# ProProject_module_robot-.net
KiCad netlist of a schematic drawn in EasyEDA Pro
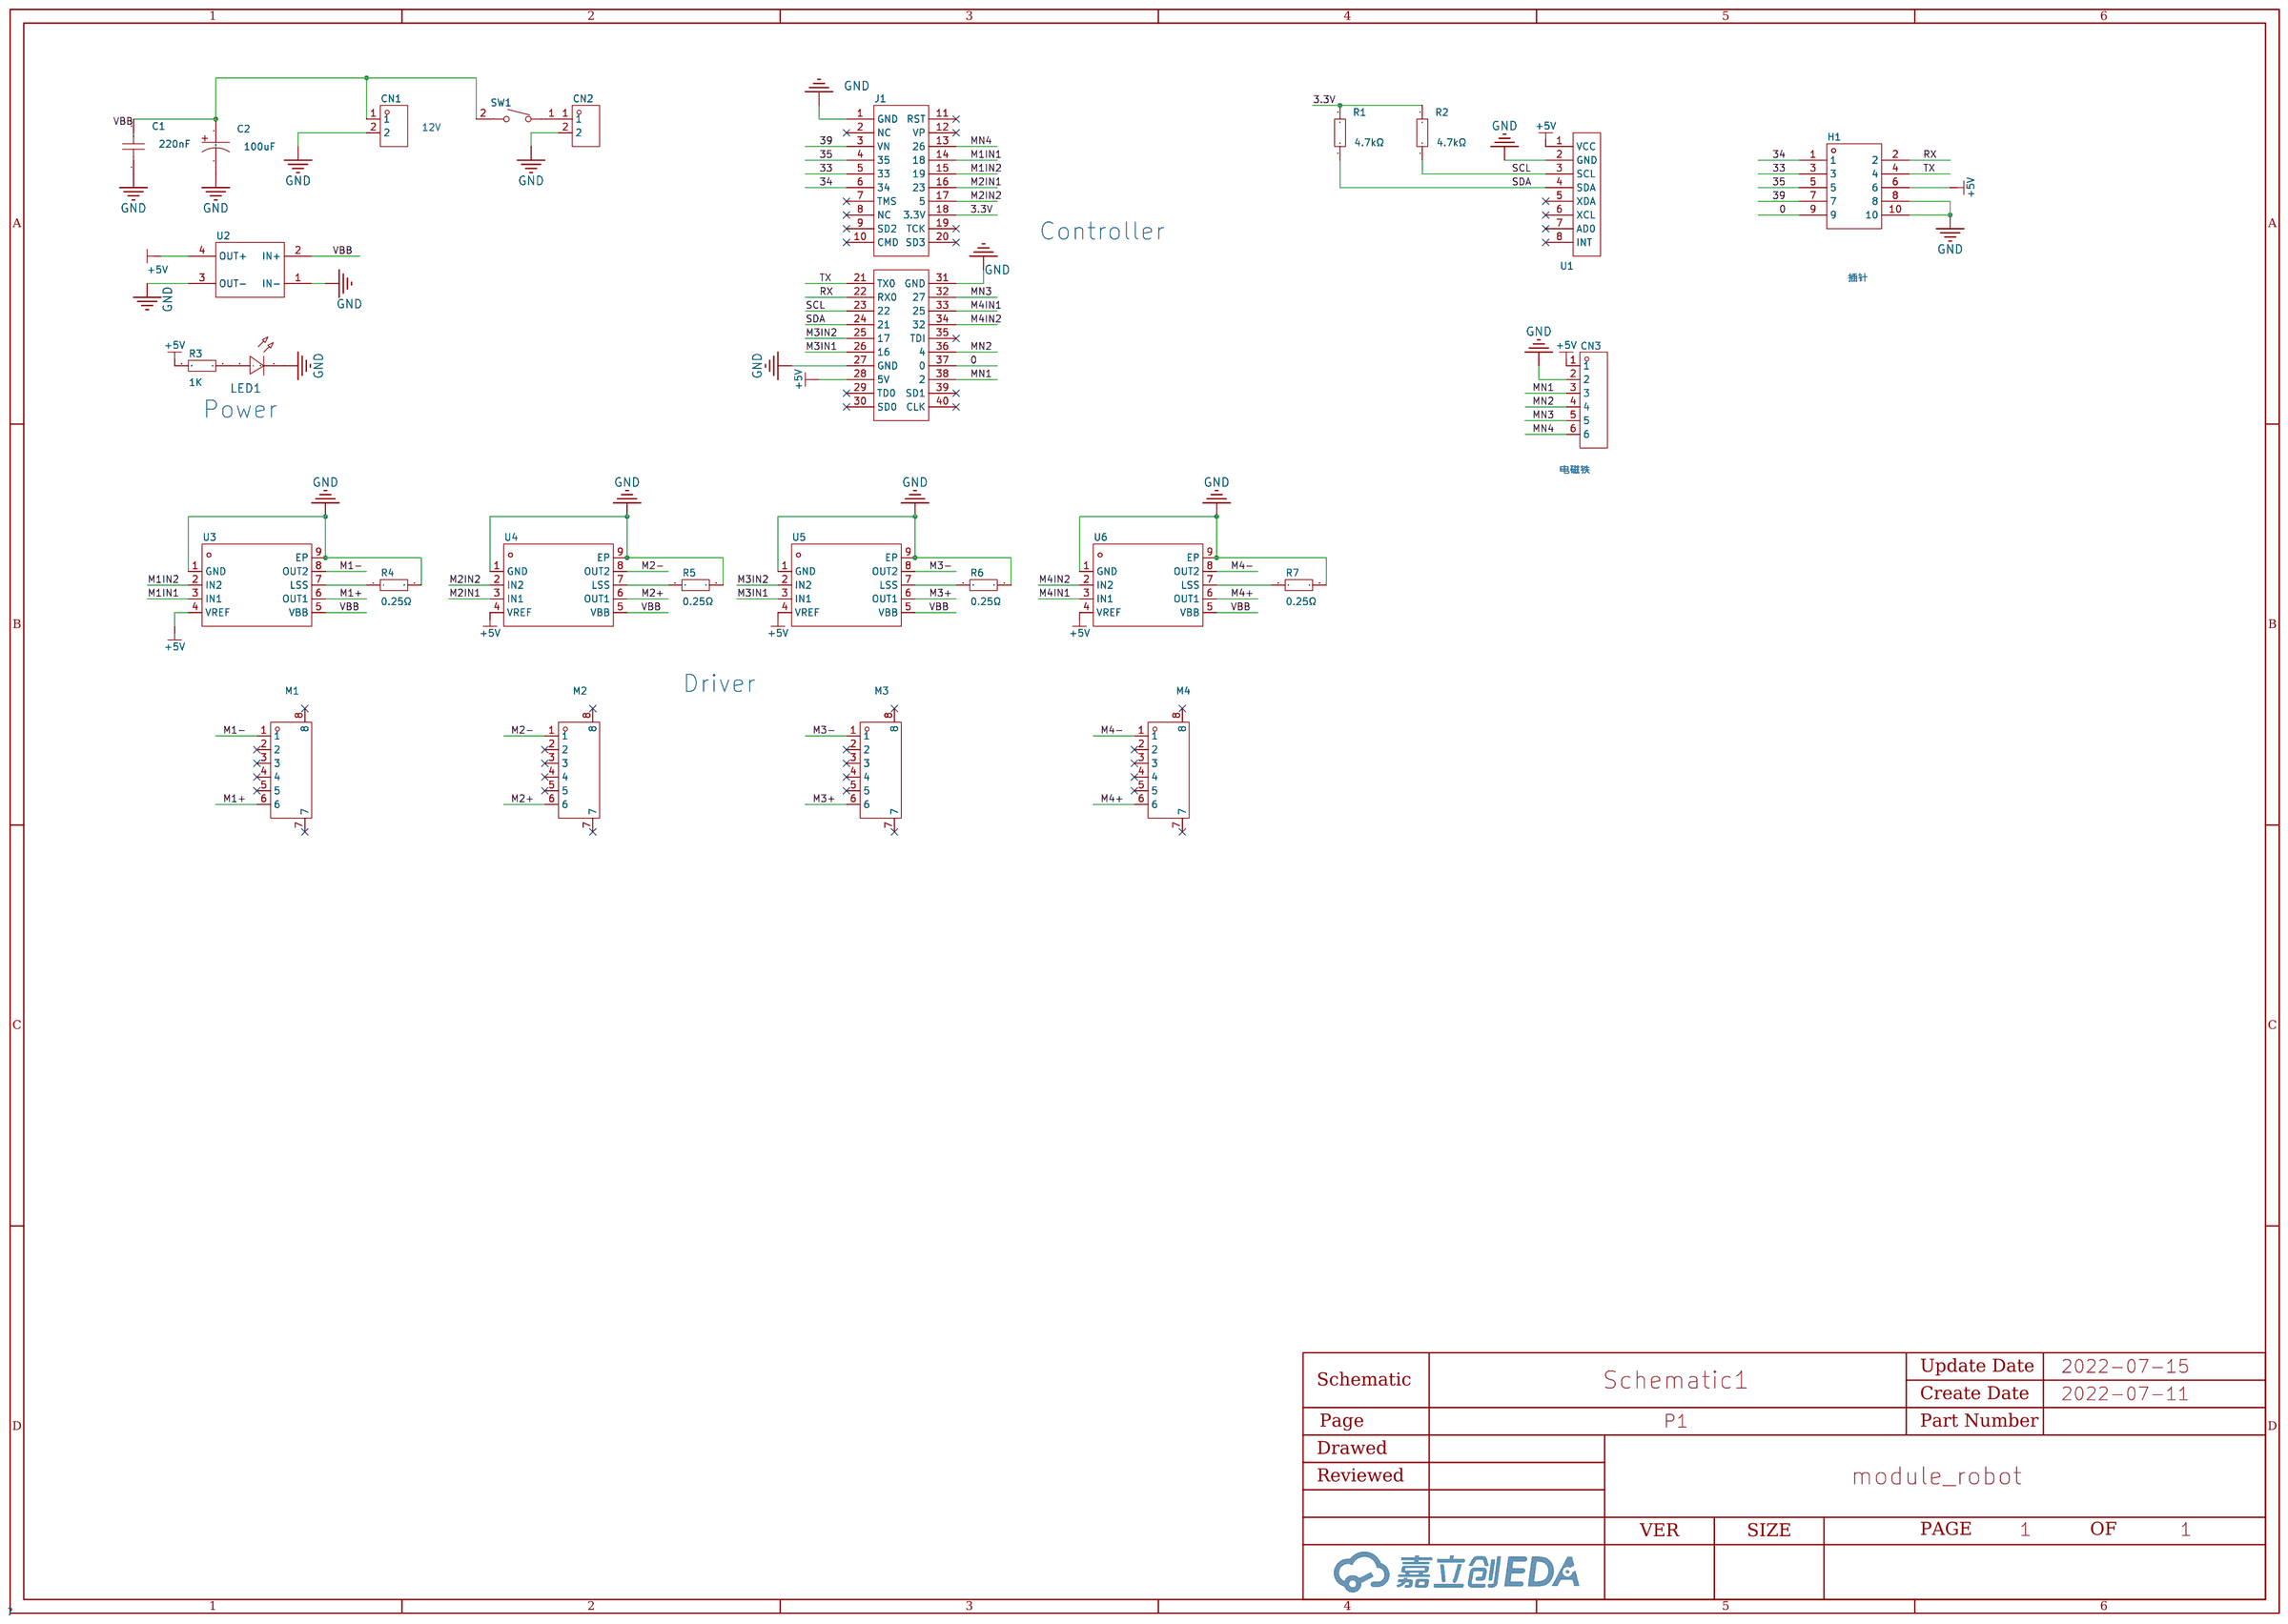
[diagram p0: schematic sheet]

(export (version "E")
  (design (tool "Eeschema 10.0.6"))
  (components
    (comp (ref "C1")
      (value "220nF")
      (description "容值:220nF;精度:±20%;额定电压:25V;温度系数:X5R;")
      (fields
        (field (name "Manufacturer Part") "TCC0603X5R224M250CT")
        (field (name "Manufacturer") "CCTC(三环)")
      )
      (libsource (lib "easyedapro") (part "TCC0603X5R224M250CT"))
    )
    (comp (ref "C2")
      (value "100uF")
      (footprint "easyedapro:CAP-TH_BD8.0-P3.50-D0.6-FD")
      (description "电容体长度:12mm;工作寿命:7000hrs 105;额定电压:50V;精度:±20%;容值:100uF;脚间距:3.5mm;电容体直径:8mm;工作温度:-;")
      (fields
        (field (name "Manufacturer Part") "RG050M101LO8*12TA-1A1E")
        (field (name "Manufacturer") "BERYL(绿宝石)")
      )
      (libsource (lib "easyedapro") (part "RG050M101LO8*12TA-1A1E"))
    )
    (comp (ref "CN1")
      (value "~")
      (footprint "easyedapro:CONN-TH_2P-P2.50_HCTL_HC-5264-2A")
      (description "参考系列:-;间距:2.5mm;插针结构:1x2P;排数:1;每排PIN数:2;行距:-;公母:公型插针;安装方式:直插;额定电流:3A;工作温度范围:-25~+85;")
      (fields (field (name "Manufacturer Part") "HC-5264-2A") (field (name "Manufacturer") "HCTL(华灿天禄)"))
      (libsource (lib "easyedapro") (part "HC-5264-2A"))
    )
    (comp (ref "CN2")
      (value "~")
      (footprint "easyedapro:CONN-TH_2P-P2.50_HCTL_HC-5264-2A")
      (description "参考系列:-;间距:2.5mm;插针结构:1x2P;排数:1;每排PIN数:2;行距:-;公母:公型插针;安装方式:直插;额定电流:3A;工作温度范围:-25~+85;")
      (fields (field (name "Manufacturer Part") "HC-5264-2A") (field (name "Manufacturer") "HCTL(华灿天禄)"))
      (libsource (lib "easyedapro") (part "HC-5264-2A"))
    )
    (comp (ref "CN3")
      (value "~")
      (footprint "easyedapro:CONN-TH_6P-P2.50_HCTL_HC-5264-6A")
      (description "参考系列:-;间距:2.5mm;插针结构:1x6P;排数:1;每排PIN数:6;行距:-;公母:公型插针;安装方式:直插;额定电流:3A;工作温度范围:-25~+85;")
      (fields (field (name "Manufacturer Part") "HC-5264-6A") (field (name "Manufacturer") "HCTL(华灿天禄)"))
      (libsource (lib "easyedapro") (part "HC-5264-6A"))
    )
    (comp (ref "H1")
      (value "~")
      (footprint "easyedapro:HDR-TH_10P-P2.54-V-M-R2-C5-S2.54")
      (libsource (lib "easyedapro") (part "HDR-M-2.54_2x5"))
    )
    (comp (ref "J1")
      (value "~")
      (description "esp32TTGO扩展封装")
      (libsource (lib "easyedapro") (part "esp32TTGO"))
    )
    (comp (ref "LED1")
      (value "~")
      (footprint "easyedapro:LED0603-RD_BLUE")
      (libsource (lib "easyedapro") (part "LED_R"))
    )
    (comp (ref "M1")
      (value "~")
      (description "参考系列:-;间距:1.5mm;插针结构:1x6P;排数:1;每排PIN数:6;行距:-;公母:公型插针;安装方式:卧贴;额定电流:500mA;工作温度范围:-25~+85;")
      (fields
        (field (name "Manufacturer Part") "KH-ZH1.5WF-06A")
        (field (name "Manufacturer") "kinghelm(金航标)")
      )
      (libsource (lib "easyedapro") (part "KH-ZH1.5WF-06A"))
    )
    (comp (ref "M2")
      (value "~")
      (description "参考系列:-;间距:1.5mm;插针结构:1x6P;排数:1;每排PIN数:6;行距:-;公母:公型插针;安装方式:卧贴;额定电流:500mA;工作温度范围:-25~+85;")
      (fields
        (field (name "Manufacturer Part") "KH-ZH1.5WF-06A")
        (field (name "Manufacturer") "kinghelm(金航标)")
      )
      (libsource (lib "easyedapro") (part "KH-ZH1.5WF-06A"))
    )
    (comp (ref "M3")
      (value "~")
      (description "参考系列:-;间距:1.5mm;插针结构:1x6P;排数:1;每排PIN数:6;行距:-;公母:公型插针;安装方式:卧贴;额定电流:500mA;工作温度范围:-25~+85;")
      (fields
        (field (name "Manufacturer Part") "KH-ZH1.5WF-06A")
        (field (name "Manufacturer") "kinghelm(金航标)")
      )
      (libsource (lib "easyedapro") (part "KH-ZH1.5WF-06A"))
    )
    (comp (ref "M4")
      (value "~")
      (description "参考系列:-;间距:1.5mm;插针结构:1x6P;排数:1;每排PIN数:6;行距:-;公母:公型插针;安装方式:卧贴;额定电流:500mA;工作温度范围:-25~+85;")
      (fields
        (field (name "Manufacturer Part") "KH-ZH1.5WF-06A")
        (field (name "Manufacturer") "kinghelm(金航标)")
      )
      (libsource (lib "easyedapro") (part "KH-ZH1.5WF-06A"))
    )
    (comp (ref "R1")
      (value "4.7kΩ")
      (footprint "easyedapro:R0805")
      (description "电阻类型:薄膜电阻;阻值:10kΩ;精度:±0.5%;功率:125mW;温度系数:±25ppm/;最大工作电压:100V;工作温度范围:-55~+155;")
      (fields (field (name "Manufacturer Part") "AR05DTCW1002") (field (name "Manufacturer") "光颉(Viking)"))
      (libsource (lib "easyedapro") (part "AR05DTCW1002"))
    )
    (comp (ref "R2")
      (value "4.7kΩ")
      (footprint "easyedapro:R0805")
      (description "电阻类型:薄膜电阻;阻值:10kΩ;精度:±0.5%;功率:125mW;温度系数:±25ppm/;最大工作电压:100V;工作温度范围:-55~+155;")
      (fields (field (name "Manufacturer Part") "AR05DTCW1002") (field (name "Manufacturer") "光颉(Viking)"))
      (libsource (lib "easyedapro") (part "AR05DTCW1002"))
    )
    (comp (ref "R3") (value "1K") (footprint "easyedapro:R0603") (libsource (lib "easyedapro") (part "电阻")))
    (comp (ref "R4")
      (value "0.25Ω")
      (description "阻值:0.25Ω;精度:±1%;功率:1W;温度系数:±600ppm/;")
      (fields
        (field (name "Manufacturer Part") "CR2512FR250E04R")
        (field (name "Manufacturer") "EVER OHMS(天二科技)")
      )
      (libsource (lib "easyedapro") (part "CR2512F0R25E04"))
    )
    (comp (ref "R5")
      (value "0.25Ω")
      (description "阻值:0.25Ω;精度:±1%;功率:1W;温度系数:±600ppm/;")
      (fields
        (field (name "Manufacturer Part") "CR2512FR250E04R")
        (field (name "Manufacturer") "EVER OHMS(天二科技)")
      )
      (libsource (lib "easyedapro") (part "CR2512F0R25E04"))
    )
    (comp (ref "R6")
      (value "0.25Ω")
      (description "阻值:0.25Ω;精度:±1%;功率:1W;温度系数:±600ppm/;")
      (fields
        (field (name "Manufacturer Part") "CR2512FR250E04R")
        (field (name "Manufacturer") "EVER OHMS(天二科技)")
      )
      (libsource (lib "easyedapro") (part "CR2512F0R25E04"))
    )
    (comp (ref "R7")
      (value "0.25Ω")
      (description "阻值:0.25Ω;精度:±1%;功率:1W;温度系数:±600ppm/;")
      (fields
        (field (name "Manufacturer Part") "CR2512FR250E04R")
        (field (name "Manufacturer") "EVER OHMS(天二科技)")
      )
      (libsource (lib "easyedapro") (part "CR2512F0R25E04"))
    )
    (comp (ref "SW1")
      (value "MR5-111-C5N-WW")
      (footprint "easyedapro:SW-TH_MR5-111-C5N-BB")
      (description "船型开关@@小型船型开关，10x15在业界少有的")
      (fields (field (name "Manufacturer") "D-SWITCH(德崧)"))
      (libsource (lib "easyedapro") (part "MR5-111-C5N-WW"))
    )
    (comp (ref "U1")
      (value "~")
      (footprint "easyedapro:MPU6050")
      (description "MPU6050外形封装")
      (libsource (lib "easyedapro") (part "MPU6050"))
    )
    (comp (ref "U2")
      (value "~")
      (footprint "easyedapro:DC-DC降压5/3.3V")
      (libsource (lib "easyedapro") (part "DC-DC降压5/3.3V"))
    )
    (comp (ref "U3")
      (value "~")
      (description "全桥DMOS PWM电机驱动器")
      (fields
        (field (name "Manufacturer Part") "A4950ELJTR-T")
        (field (name "Manufacturer") "ALLEGRO(美国埃戈罗)")
      )
      (libsource (lib "easyedapro") (part "A4950ELJTR-T"))
    )
    (comp (ref "U4")
      (value "~")
      (description "全桥DMOS PWM电机驱动器")
      (fields
        (field (name "Manufacturer Part") "A4950ELJTR-T")
        (field (name "Manufacturer") "ALLEGRO(美国埃戈罗)")
      )
      (libsource (lib "easyedapro") (part "A4950ELJTR-T"))
    )
    (comp (ref "U5")
      (value "~")
      (description "全桥DMOS PWM电机驱动器")
      (fields
        (field (name "Manufacturer Part") "A4950ELJTR-T")
        (field (name "Manufacturer") "ALLEGRO(美国埃戈罗)")
      )
      (libsource (lib "easyedapro") (part "A4950ELJTR-T"))
    )
    (comp (ref "U6")
      (value "~")
      (description "全桥DMOS PWM电机驱动器")
      (fields
        (field (name "Manufacturer Part") "A4950ELJTR-T")
        (field (name "Manufacturer") "ALLEGRO(美国埃戈罗)")
      )
      (libsource (lib "easyedapro") (part "A4950ELJTR-T"))
    )
  )
  (nets
    (net (code "1") (name "+5V") (class "Default")
      (node (ref "CN3") (pin "1") (pinfunction "1_1") (pintype "input"))
      (node (ref "H1") (pin "6") (pinfunction "6_6") (pintype "input"))
      (node (ref "J1") (pin "28") (pinfunction "5V_28") (pintype "input"))
      (node (ref "R3") (pin "1") (pinfunction "1_1") (pintype "input"))
      (node (ref "U1") (pin "1") (pinfunction "VCC_1") (pintype "input"))
      (node (ref "U2") (pin "4") (pinfunction "OUT+_4") (pintype "input"))
      (node (ref "U3") (pin "4") (pinfunction "VREF_4") (pintype "input"))
      (node (ref "U4") (pin "4") (pinfunction "VREF_4") (pintype "input"))
      (node (ref "U5") (pin "4") (pinfunction "VREF_4") (pintype "input"))
      (node (ref "U6") (pin "4") (pinfunction "VREF_4") (pintype "input"))
    )
    (net (code "2") (name "/0") (class "Default")
      (node (ref "H1") (pin "9") (pinfunction "9_9") (pintype "input"))
      (node (ref "J1") (pin "37") (pinfunction "0_37") (pintype "input"))
    )
    (net (code "3") (name "/3.3V") (class "Default")
      (node (ref "J1") (pin "18") (pinfunction "3.3V_18") (pintype "input"))
      (node (ref "R1") (pin "2") (pinfunction "2_2") (pintype "input"))
      (node (ref "R2") (pin "2") (pinfunction "2_2") (pintype "input"))
    )
    (net (code "4") (name "/33") (class "Default")
      (node (ref "H1") (pin "3") (pinfunction "3_3") (pintype "input"))
      (node (ref "J1") (pin "5") (pinfunction "33_5") (pintype "input"))
    )
    (net (code "5") (name "/34") (class "Default")
      (node (ref "H1") (pin "1") (pinfunction "1_1") (pintype "input"))
      (node (ref "J1") (pin "6") (pinfunction "34_6") (pintype "input"))
    )
    (net (code "6") (name "/35") (class "Default")
      (node (ref "H1") (pin "5") (pinfunction "5_5") (pintype "input"))
      (node (ref "J1") (pin "4") (pinfunction "35_4") (pintype "input"))
    )
    (net (code "7") (name "/39") (class "Default")
      (node (ref "H1") (pin "7") (pinfunction "7_7") (pintype "input"))
      (node (ref "J1") (pin "3") (pinfunction "VN_3") (pintype "input"))
    )
    (net (code "8") (name "/M1+") (class "Default")
      (node (ref "M1") (pin "6") (pinfunction "6_6") (pintype "input"))
      (node (ref "U3") (pin "6") (pinfunction "OUT1_6") (pintype "input"))
    )
    (net (code "9") (name "/M1-") (class "Default")
      (node (ref "M1") (pin "1") (pinfunction "1_1") (pintype "input"))
      (node (ref "U3") (pin "8") (pinfunction "OUT2_8") (pintype "input"))
    )
    (net (code "10") (name "/M1IN1") (class "Default")
      (node (ref "J1") (pin "14") (pinfunction "18_14") (pintype "input"))
      (node (ref "U3") (pin "3") (pinfunction "IN1_3") (pintype "input"))
    )
    (net (code "11") (name "/M1IN2") (class "Default")
      (node (ref "J1") (pin "15") (pinfunction "19_15") (pintype "input"))
      (node (ref "U3") (pin "2") (pinfunction "IN2_2") (pintype "input"))
    )
    (net (code "12") (name "/M2+") (class "Default")
      (node (ref "M2") (pin "6") (pinfunction "6_6") (pintype "input"))
      (node (ref "U4") (pin "6") (pinfunction "OUT1_6") (pintype "input"))
    )
    (net (code "13") (name "/M2-") (class "Default")
      (node (ref "M2") (pin "1") (pinfunction "1_1") (pintype "input"))
      (node (ref "U4") (pin "8") (pinfunction "OUT2_8") (pintype "input"))
    )
    (net (code "14") (name "/M2IN1") (class "Default")
      (node (ref "J1") (pin "16") (pinfunction "23_16") (pintype "input"))
      (node (ref "U4") (pin "3") (pinfunction "IN1_3") (pintype "input"))
    )
    (net (code "15") (name "/M2IN2") (class "Default")
      (node (ref "J1") (pin "17") (pinfunction "5_17") (pintype "input"))
      (node (ref "U4") (pin "2") (pinfunction "IN2_2") (pintype "input"))
    )
    (net (code "16") (name "/M3+") (class "Default")
      (node (ref "M3") (pin "6") (pinfunction "6_6") (pintype "input"))
      (node (ref "U5") (pin "6") (pinfunction "OUT1_6") (pintype "input"))
    )
    (net (code "17") (name "/M3-") (class "Default")
      (node (ref "M3") (pin "1") (pinfunction "1_1") (pintype "input"))
      (node (ref "U5") (pin "8") (pinfunction "OUT2_8") (pintype "input"))
    )
    (net (code "18") (name "/M3IN1") (class "Default")
      (node (ref "J1") (pin "26") (pinfunction "16_26") (pintype "input"))
      (node (ref "U5") (pin "3") (pinfunction "IN1_3") (pintype "input"))
    )
    (net (code "19") (name "/M3IN2") (class "Default")
      (node (ref "J1") (pin "25") (pinfunction "17_25") (pintype "input"))
      (node (ref "U5") (pin "2") (pinfunction "IN2_2") (pintype "input"))
    )
    (net (code "20") (name "/M4+") (class "Default")
      (node (ref "M4") (pin "6") (pinfunction "6_6") (pintype "input"))
      (node (ref "U6") (pin "6") (pinfunction "OUT1_6") (pintype "input"))
    )
    (net (code "21") (name "/M4-") (class "Default")
      (node (ref "M4") (pin "1") (pinfunction "1_1") (pintype "input"))
      (node (ref "U6") (pin "8") (pinfunction "OUT2_8") (pintype "input"))
    )
    (net (code "22") (name "/M4IN1") (class "Default")
      (node (ref "J1") (pin "33") (pinfunction "25_33") (pintype "input"))
      (node (ref "U6") (pin "3") (pinfunction "IN1_3") (pintype "input"))
    )
    (net (code "23") (name "/M4IN2") (class "Default")
      (node (ref "J1") (pin "34") (pinfunction "32_34") (pintype "input"))
      (node (ref "U6") (pin "2") (pinfunction "IN2_2") (pintype "input"))
    )
    (net (code "24") (name "/MN1") (class "Default")
      (node (ref "CN3") (pin "3") (pinfunction "3_3") (pintype "input"))
      (node (ref "J1") (pin "38") (pinfunction "2_38") (pintype "input"))
    )
    (net (code "25") (name "/MN2") (class "Default")
      (node (ref "CN3") (pin "4") (pinfunction "4_4") (pintype "input"))
      (node (ref "J1") (pin "36") (pinfunction "4_36") (pintype "input"))
    )
    (net (code "26") (name "/MN3") (class "Default")
      (node (ref "CN3") (pin "5") (pinfunction "5_5") (pintype "input"))
      (node (ref "J1") (pin "32") (pinfunction "27_32") (pintype "input"))
    )
    (net (code "27") (name "/MN4") (class "Default")
      (node (ref "CN3") (pin "6") (pinfunction "6_6") (pintype "input"))
      (node (ref "J1") (pin "13") (pinfunction "26_13") (pintype "input"))
    )
    (net (code "28") (name "/RX") (class "Default")
      (node (ref "H1") (pin "2") (pinfunction "2_2") (pintype "input"))
      (node (ref "J1") (pin "22") (pinfunction "RX0_22") (pintype "input"))
    )
    (net (code "29") (name "/SCL") (class "Default")
      (node (ref "J1") (pin "23") (pinfunction "22_23") (pintype "input"))
      (node (ref "R2") (pin "1") (pinfunction "1_1") (pintype "input"))
      (node (ref "U1") (pin "3") (pinfunction "SCL_3") (pintype "input"))
    )
    (net (code "30") (name "/SDA") (class "Default")
      (node (ref "J1") (pin "24") (pinfunction "21_24") (pintype "input"))
      (node (ref "R1") (pin "1") (pinfunction "1_1") (pintype "input"))
      (node (ref "U1") (pin "4") (pinfunction "SDA_4") (pintype "input"))
    )
    (net (code "31") (name "/TX") (class "Default")
      (node (ref "H1") (pin "4") (pinfunction "4_4") (pintype "input"))
      (node (ref "J1") (pin "21") (pinfunction "TX0_21") (pintype "input"))
    )
    (net (code "32") (name "/VBB") (class "Default")
      (node (ref "C1") (pin "2") (pinfunction "2_2") (pintype "input"))
      (node (ref "C2") (pin "1") (pinfunction "1_1") (pintype "input"))
      (node (ref "CN1") (pin "1") (pinfunction "1_1") (pintype "input"))
      (node (ref "SW1") (pin "2") (pinfunction "2_2") (pintype "input"))
      (node (ref "U2") (pin "2") (pinfunction "IN+_2") (pintype "input"))
      (node (ref "U3") (pin "5") (pinfunction "VBB_5") (pintype "input"))
      (node (ref "U4") (pin "5") (pinfunction "VBB_5") (pintype "input"))
      (node (ref "U5") (pin "5") (pinfunction "VBB_5") (pintype "input"))
      (node (ref "U6") (pin "5") (pinfunction "VBB_5") (pintype "input"))
    )
    (net (code "33") (name "GND") (class "Default")
      (node (ref "C1") (pin "1") (pinfunction "1_1") (pintype "input"))
      (node (ref "C2") (pin "2") (pinfunction "2_2") (pintype "input"))
      (node (ref "CN1") (pin "2") (pinfunction "2_2") (pintype "input"))
      (node (ref "CN2") (pin "2") (pinfunction "2_2") (pintype "input"))
      (node (ref "CN3") (pin "2") (pinfunction "2_2") (pintype "input"))
      (node (ref "H1") (pin "10") (pinfunction "10_10") (pintype "input"))
      (node (ref "H1") (pin "8") (pinfunction "8_8") (pintype "input"))
      (node (ref "J1") (pin "1") (pinfunction "GND_1") (pintype "input"))
      (node (ref "J1") (pin "27") (pinfunction "GND_27") (pintype "input"))
      (node (ref "J1") (pin "31") (pinfunction "GND_31") (pintype "input"))
      (node (ref "LED1") (pin "1") (pinfunction "C_1") (pintype "input"))
      (node (ref "R4") (pin "2") (pinfunction "2_2") (pintype "input"))
      (node (ref "R5") (pin "2") (pinfunction "2_2") (pintype "input"))
      (node (ref "R6") (pin "2") (pinfunction "2_2") (pintype "input"))
      (node (ref "R7") (pin "2") (pinfunction "2_2") (pintype "input"))
      (node (ref "U1") (pin "2") (pinfunction "GND_2") (pintype "input"))
      (node (ref "U2") (pin "1") (pinfunction "IN-_1") (pintype "input"))
      (node (ref "U2") (pin "3") (pinfunction "OUT-_3") (pintype "input"))
      (node (ref "U3") (pin "1") (pinfunction "GND_1") (pintype "input"))
      (node (ref "U3") (pin "9") (pinfunction "EP_9") (pintype "input"))
      (node (ref "U4") (pin "1") (pinfunction "GND_1") (pintype "input"))
      (node (ref "U4") (pin "9") (pinfunction "EP_9") (pintype "input"))
      (node (ref "U5") (pin "1") (pinfunction "GND_1") (pintype "input"))
      (node (ref "U5") (pin "9") (pinfunction "EP_9") (pintype "input"))
      (node (ref "U6") (pin "1") (pinfunction "GND_1") (pintype "input"))
      (node (ref "U6") (pin "9") (pinfunction "EP_9") (pintype "input"))
    )
    (net (code "34") (name "Net-(CN2-Pad1)") (class "Default")
      (node (ref "CN2") (pin "1") (pinfunction "1_1") (pintype "input"))
      (node (ref "SW1") (pin "1") (pinfunction "1_1") (pintype "input"))
    )
    (net (code "35") (name "Net-(LED1-A)") (class "Default")
      (node (ref "LED1") (pin "2") (pinfunction "A_2") (pintype "input"))
      (node (ref "R3") (pin "2") (pinfunction "2_2") (pintype "input"))
    )
    (net (code "36") (name "Net-(U3-LSS)") (class "Default")
      (node (ref "R4") (pin "1") (pinfunction "1_1") (pintype "input"))
      (node (ref "U3") (pin "7") (pinfunction "LSS_7") (pintype "input"))
    )
    (net (code "37") (name "Net-(U4-LSS)") (class "Default")
      (node (ref "R5") (pin "1") (pinfunction "1_1") (pintype "input"))
      (node (ref "U4") (pin "7") (pinfunction "LSS_7") (pintype "input"))
    )
    (net (code "38") (name "Net-(U5-LSS)") (class "Default")
      (node (ref "R6") (pin "1") (pinfunction "1_1") (pintype "input"))
      (node (ref "U5") (pin "7") (pinfunction "LSS_7") (pintype "input"))
    )
    (net (code "39") (name "Net-(U6-LSS)") (class "Default")
      (node (ref "R7") (pin "1") (pinfunction "1_1") (pintype "input"))
      (node (ref "U6") (pin "7") (pinfunction "LSS_7") (pintype "input"))
    )
    (net (code "40") (name "unconnected-(J1-CLK-Pad40)") (class "Default")
      (node (ref "J1") (pin "40") (pinfunction "CLK_40") (pintype "input+no_connect"))
    )
    (net (code "41") (name "unconnected-(J1-CMD-Pad10)") (class "Default")
      (node (ref "J1") (pin "10") (pinfunction "CMD_10") (pintype "input+no_connect"))
    )
    (net (code "42") (name "unconnected-(J1-NC-Pad2)") (class "Default")
      (node (ref "J1") (pin "2") (pinfunction "NC_2") (pintype "input+no_connect"))
    )
    (net (code "43") (name "unconnected-(J1-NC-Pad8)") (class "Default")
      (node (ref "J1") (pin "8") (pinfunction "NC_8") (pintype "input+no_connect"))
    )
    (net (code "44") (name "unconnected-(J1-RST-Pad11)") (class "Default")
      (node (ref "J1") (pin "11") (pinfunction "RST_11") (pintype "input+no_connect"))
    )
    (net (code "45") (name "unconnected-(J1-SD0-Pad30)") (class "Default")
      (node (ref "J1") (pin "30") (pinfunction "SD0_30") (pintype "input+no_connect"))
    )
    (net (code "46") (name "unconnected-(J1-SD1-Pad39)") (class "Default")
      (node (ref "J1") (pin "39") (pinfunction "SD1_39") (pintype "input+no_connect"))
    )
    (net (code "47") (name "unconnected-(J1-SD2-Pad9)") (class "Default")
      (node (ref "J1") (pin "9") (pinfunction "SD2_9") (pintype "input+no_connect"))
    )
    (net (code "48") (name "unconnected-(J1-SD3-Pad20)") (class "Default")
      (node (ref "J1") (pin "20") (pinfunction "SD3_20") (pintype "input+no_connect"))
    )
    (net (code "49") (name "unconnected-(J1-TCK-Pad19)") (class "Default")
      (node (ref "J1") (pin "19") (pinfunction "TCK_19") (pintype "input+no_connect"))
    )
    (net (code "50") (name "unconnected-(J1-TD0-Pad29)") (class "Default")
      (node (ref "J1") (pin "29") (pinfunction "TD0_29") (pintype "input+no_connect"))
    )
    (net (code "51") (name "unconnected-(J1-TDI-Pad35)") (class "Default")
      (node (ref "J1") (pin "35") (pinfunction "TDI_35") (pintype "input+no_connect"))
    )
    (net (code "52") (name "unconnected-(J1-TMS-Pad7)") (class "Default")
      (node (ref "J1") (pin "7") (pinfunction "TMS_7") (pintype "input+no_connect"))
    )
    (net (code "53") (name "unconnected-(J1-VP-Pad12)") (class "Default")
      (node (ref "J1") (pin "12") (pinfunction "VP_12") (pintype "input+no_connect"))
    )
    (net (code "54") (name "unconnected-(M1-Pad2)") (class "Default")
      (node (ref "M1") (pin "2") (pinfunction "2_2") (pintype "input+no_connect"))
    )
    (net (code "55") (name "unconnected-(M1-Pad3)") (class "Default")
      (node (ref "M1") (pin "3") (pinfunction "3_3") (pintype "input+no_connect"))
    )
    (net (code "56") (name "unconnected-(M1-Pad4)") (class "Default")
      (node (ref "M1") (pin "4") (pinfunction "4_4") (pintype "input+no_connect"))
    )
    (net (code "57") (name "unconnected-(M1-Pad5)") (class "Default")
      (node (ref "M1") (pin "5") (pinfunction "5_5") (pintype "input+no_connect"))
    )
    (net (code "58") (name "unconnected-(M1-Pad7)") (class "Default")
      (node (ref "M1") (pin "7") (pinfunction "7_7") (pintype "input+no_connect"))
    )
    (net (code "59") (name "unconnected-(M1-Pad8)") (class "Default")
      (node (ref "M1") (pin "8") (pinfunction "8_8") (pintype "input+no_connect"))
    )
    (net (code "60") (name "unconnected-(M2-Pad2)") (class "Default")
      (node (ref "M2") (pin "2") (pinfunction "2_2") (pintype "input+no_connect"))
    )
    (net (code "61") (name "unconnected-(M2-Pad3)") (class "Default")
      (node (ref "M2") (pin "3") (pinfunction "3_3") (pintype "input+no_connect"))
    )
    (net (code "62") (name "unconnected-(M2-Pad4)") (class "Default")
      (node (ref "M2") (pin "4") (pinfunction "4_4") (pintype "input+no_connect"))
    )
    (net (code "63") (name "unconnected-(M2-Pad5)") (class "Default")
      (node (ref "M2") (pin "5") (pinfunction "5_5") (pintype "input+no_connect"))
    )
    (net (code "64") (name "unconnected-(M2-Pad7)") (class "Default")
      (node (ref "M2") (pin "7") (pinfunction "7_7") (pintype "input+no_connect"))
    )
    (net (code "65") (name "unconnected-(M2-Pad8)") (class "Default")
      (node (ref "M2") (pin "8") (pinfunction "8_8") (pintype "input+no_connect"))
    )
    (net (code "66") (name "unconnected-(M3-Pad2)") (class "Default")
      (node (ref "M3") (pin "2") (pinfunction "2_2") (pintype "input+no_connect"))
    )
    (net (code "67") (name "unconnected-(M3-Pad3)") (class "Default")
      (node (ref "M3") (pin "3") (pinfunction "3_3") (pintype "input+no_connect"))
    )
    (net (code "68") (name "unconnected-(M3-Pad4)") (class "Default")
      (node (ref "M3") (pin "4") (pinfunction "4_4") (pintype "input+no_connect"))
    )
    (net (code "69") (name "unconnected-(M3-Pad5)") (class "Default")
      (node (ref "M3") (pin "5") (pinfunction "5_5") (pintype "input+no_connect"))
    )
    (net (code "70") (name "unconnected-(M3-Pad7)") (class "Default")
      (node (ref "M3") (pin "7") (pinfunction "7_7") (pintype "input+no_connect"))
    )
    (net (code "71") (name "unconnected-(M3-Pad8)") (class "Default")
      (node (ref "M3") (pin "8") (pinfunction "8_8") (pintype "input+no_connect"))
    )
    (net (code "72") (name "unconnected-(M4-Pad2)") (class "Default")
      (node (ref "M4") (pin "2") (pinfunction "2_2") (pintype "input+no_connect"))
    )
    (net (code "73") (name "unconnected-(M4-Pad3)") (class "Default")
      (node (ref "M4") (pin "3") (pinfunction "3_3") (pintype "input+no_connect"))
    )
    (net (code "74") (name "unconnected-(M4-Pad4)") (class "Default")
      (node (ref "M4") (pin "4") (pinfunction "4_4") (pintype "input+no_connect"))
    )
    (net (code "75") (name "unconnected-(M4-Pad5)") (class "Default")
      (node (ref "M4") (pin "5") (pinfunction "5_5") (pintype "input+no_connect"))
    )
    (net (code "76") (name "unconnected-(M4-Pad7)") (class "Default")
      (node (ref "M4") (pin "7") (pinfunction "7_7") (pintype "input+no_connect"))
    )
    (net (code "77") (name "unconnected-(M4-Pad8)") (class "Default")
      (node (ref "M4") (pin "8") (pinfunction "8_8") (pintype "input+no_connect"))
    )
    (net (code "78") (name "unconnected-(U1-AD0-Pad7)") (class "Default")
      (node (ref "U1") (pin "7") (pinfunction "AD0_7") (pintype "input+no_connect"))
    )
    (net (code "79") (name "unconnected-(U1-INT-Pad8)") (class "Default")
      (node (ref "U1") (pin "8") (pinfunction "INT_8") (pintype "input+no_connect"))
    )
    (net (code "80") (name "unconnected-(U1-XCL-Pad6)") (class "Default")
      (node (ref "U1") (pin "6") (pinfunction "XCL_6") (pintype "input+no_connect"))
    )
    (net (code "81") (name "unconnected-(U1-XDA-Pad5)") (class "Default")
      (node (ref "U1") (pin "5") (pinfunction "XDA_5") (pintype "input+no_connect"))
    )
  )
)
